# STM32.net
KiCad netlist of a schematic drawn in Altium Designer
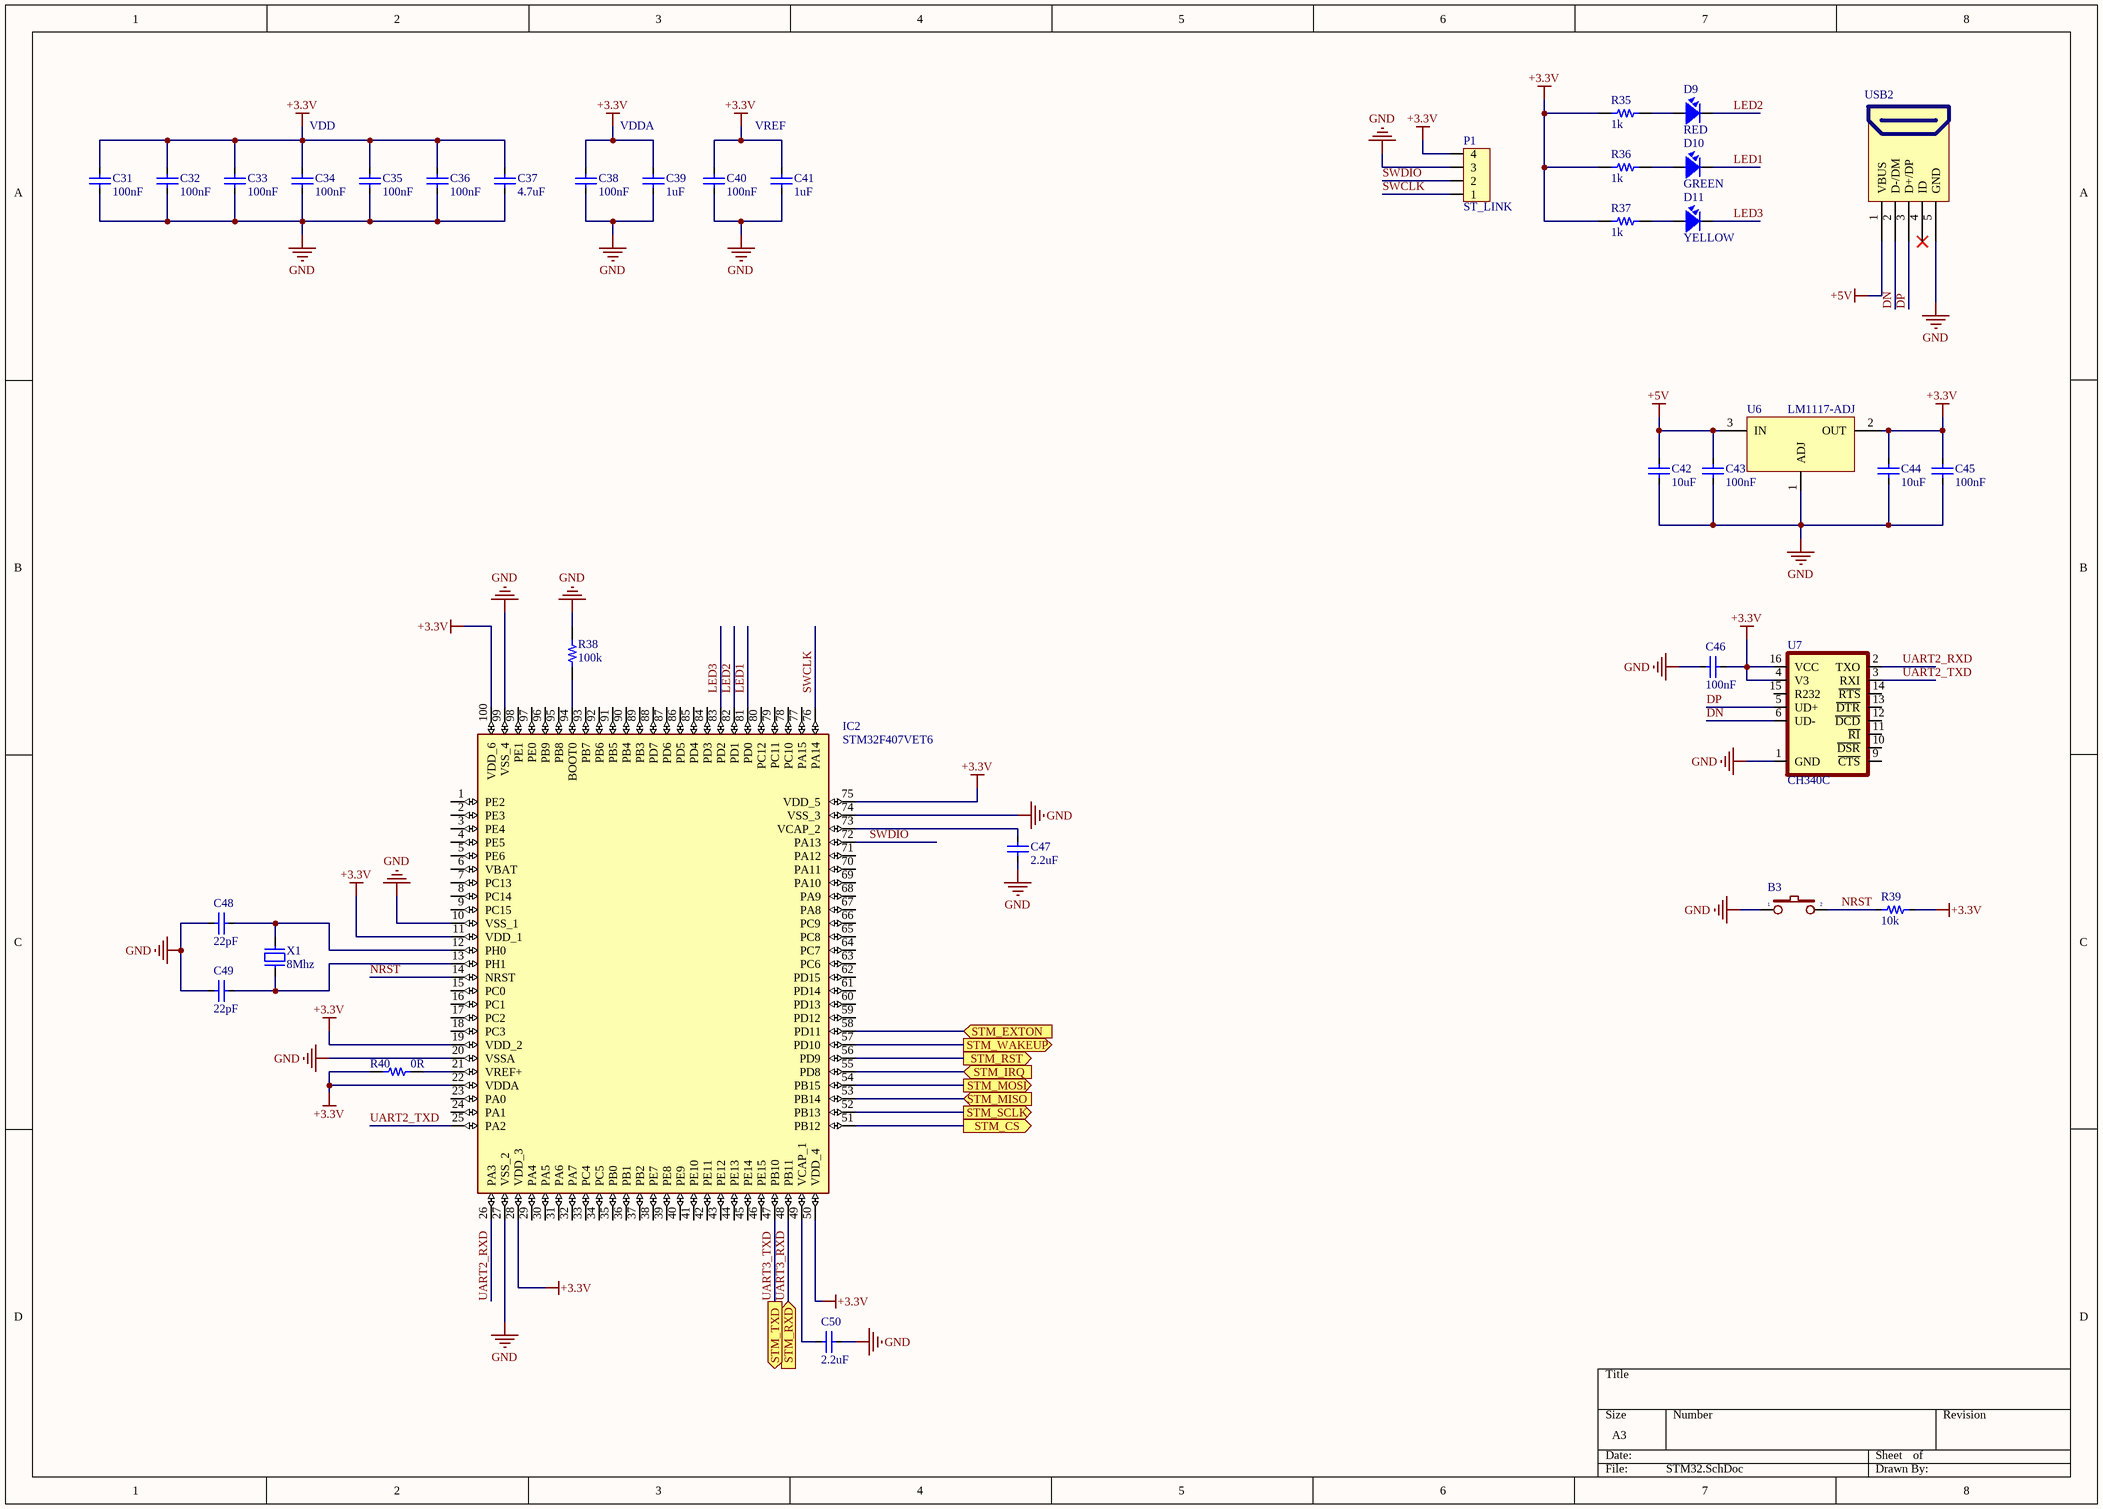
[diagram p0: STM32.SchDoc]

(export (version "E")
  (design (tool "Eeschema 10.0.6"))
  (components
    (comp (ref "B3")
      (value "Button 3x4x2.5")
      (footprint "Button 3x4x2.5")
      (libsource (lib "Dung Library") (part "Button 3x4x2.5"))
    )
    (comp (ref "C31")
      (value "100nF")
      (footprint "CAP_0603")
      (description "Capacitor")
      (fields (field (name "PUBLISHER") "Altium Limited"))
      (libsource (lib "My Library") (part "CapSMD"))
    )
    (comp (ref "C32")
      (value "100nF")
      (footprint "CAP_0603")
      (description "Capacitor")
      (fields (field (name "PUBLISHER") "Altium Limited"))
      (libsource (lib "My Library") (part "CapSMD"))
    )
    (comp (ref "C33")
      (value "100nF")
      (footprint "CAP_0603")
      (description "Capacitor")
      (fields (field (name "PUBLISHER") "Altium Limited"))
      (libsource (lib "My Library") (part "CapSMD"))
    )
    (comp (ref "C34")
      (value "100nF")
      (footprint "CAP_0603")
      (description "Capacitor")
      (fields (field (name "PUBLISHER") "Altium Limited"))
      (libsource (lib "My Library") (part "CapSMD"))
    )
    (comp (ref "C35")
      (value "100nF")
      (footprint "CAP_0603")
      (description "Capacitor")
      (fields (field (name "PUBLISHER") "Altium Limited"))
      (libsource (lib "My Library") (part "CapSMD"))
    )
    (comp (ref "C36")
      (value "100nF")
      (footprint "CAP_0603")
      (description "Capacitor")
      (fields (field (name "PUBLISHER") "Altium Limited"))
      (libsource (lib "My Library") (part "CapSMD"))
    )
    (comp (ref "C37")
      (value "4.7uF")
      (footprint "CAP_0603")
      (description "Capacitor")
      (fields (field (name "PUBLISHER") "Altium Limited"))
      (libsource (lib "My Library") (part "CapSMD"))
    )
    (comp (ref "C38")
      (value "100nF")
      (footprint "CAP_0603")
      (description "Capacitor")
      (fields (field (name "PUBLISHER") "Altium Limited"))
      (libsource (lib "My Library") (part "CapSMD"))
    )
    (comp (ref "C39")
      (value "1uF")
      (footprint "CAP_0603")
      (description "Capacitor")
      (fields (field (name "PUBLISHER") "Altium Limited"))
      (libsource (lib "My Library") (part "CapSMD"))
    )
    (comp (ref "C40")
      (value "100nF")
      (footprint "CAP_0603")
      (description "Capacitor")
      (fields (field (name "PUBLISHER") "Altium Limited"))
      (libsource (lib "My Library") (part "CapSMD"))
    )
    (comp (ref "C41")
      (value "1uF")
      (footprint "CAP_0603")
      (description "Capacitor")
      (fields (field (name "PUBLISHER") "Altium Limited"))
      (libsource (lib "My Library") (part "CapSMD"))
    )
    (comp (ref "C42")
      (value "10uF")
      (footprint "CAP_0603")
      (description "Capacitor")
      (fields (field (name "PUBLISHER") "Altium Limited"))
      (libsource (lib "My Library") (part "CapSMD"))
    )
    (comp (ref "C43")
      (value "100nF")
      (footprint "CAP_0603")
      (description "Capacitor")
      (fields (field (name "PUBLISHER") "Altium Limited"))
      (libsource (lib "My Library") (part "CapSMD"))
    )
    (comp (ref "C44")
      (value "10uF")
      (footprint "CAP_0603")
      (description "Capacitor")
      (fields (field (name "PUBLISHER") "Altium Limited"))
      (libsource (lib "My Library") (part "CapSMD"))
    )
    (comp (ref "C45")
      (value "100nF")
      (footprint "CAP_0603")
      (description "Capacitor")
      (fields (field (name "PUBLISHER") "Altium Limited"))
      (libsource (lib "My Library") (part "CapSMD"))
    )
    (comp (ref "C46")
      (value "100nF")
      (footprint "CAP_0603")
      (description "Capacitor")
      (fields (field (name "PUBLISHER") "Altium Limited"))
      (libsource (lib "My Library") (part "CapSMD"))
    )
    (comp (ref "C47")
      (value "2.2uF")
      (footprint "CAP_0603")
      (description "Capacitor")
      (fields (field (name "PUBLISHER") "Altium Limited"))
      (libsource (lib "My Library") (part "CapSMD"))
    )
    (comp (ref "C48")
      (value "22pF")
      (footprint "CAP_0603")
      (description "Capacitor")
      (fields (field (name "PUBLISHER") "Altium Limited"))
      (libsource (lib "My Library") (part "CapSMD"))
    )
    (comp (ref "C49")
      (value "22pF")
      (footprint "CAP_0603")
      (description "Capacitor")
      (fields (field (name "PUBLISHER") "Altium Limited"))
      (libsource (lib "My Library") (part "CapSMD"))
    )
    (comp (ref "C50")
      (value "2.2uF")
      (footprint "CAP_0603")
      (description "Capacitor")
      (fields (field (name "PUBLISHER") "Altium Limited"))
      (libsource (lib "My Library") (part "CapSMD"))
    )
    (comp (ref "D9")
      (value "RED")
      (footprint "LED-0603-Red")
      (description "LED Single colour Green and Red")
      (libsource (lib "My Library") (part "LED"))
    )
    (comp (ref "D10")
      (value "GREEN")
      (footprint "LED-0603-Green")
      (description "LED Single colour Green and Red")
      (libsource (lib "My Library") (part "LED"))
    )
    (comp (ref "D11")
      (value "YELLOW")
      (footprint "LED-0603-Red")
      (description "LED Single colour Green and Red")
      (libsource (lib "My Library") (part "LED"))
    )
    (comp (ref "IC2")
      (value "STM32F407VET6")
      (footprint "STM32F407VET6")
      (libsource (lib "Dung Library") (part "STM32F407VET6"))
    )
    (comp (ref "P1")
      (value "ST_LINK")
      (footprint "HEADER4P-1.25")
      (description "Header IDC, 4 x 1 Pin Vertical 2.54mm Pitch (Non-Boxed, Male)")
      (fields
        (field (name "MANUFACTURER") "Würth Elektronik eiSos GmbH")
        (field (name "PARTNO") "613002143121")
        (field (name "CREATED BY") "Karrer Zheng")
      )
      (libsource (lib "My Library") (part "Header4"))
    )
    (comp (ref "R35")
      (value "1k")
      (footprint "RES-SMD-0603")
      (description "Resistor")
      (fields
        (field (name "MANUFACTURER") "Generic Components")
        (field (name "PUBLISHER") "Altium Hobart Technology Centre")
      )
      (libsource (lib "") (part "Resistor - SMD_1"))
    )
    (comp (ref "R36")
      (value "1k")
      (footprint "RES-SMD-0603")
      (description "Resistor")
      (fields
        (field (name "MANUFACTURER") "Generic Components")
        (field (name "PUBLISHER") "Altium Hobart Technology Centre")
      )
      (libsource (lib "") (part "Resistor - SMD_1"))
    )
    (comp (ref "R37")
      (value "1k")
      (footprint "RES-SMD-0603")
      (description "Resistor")
      (fields
        (field (name "MANUFACTURER") "Generic Components")
        (field (name "PUBLISHER") "Altium Hobart Technology Centre")
      )
      (libsource (lib "") (part "Resistor - SMD_1"))
    )
    (comp (ref "R38")
      (value "100k")
      (footprint "RES-SMD-0603")
      (description "Resistor")
      (fields
        (field (name "MANUFACTURER") "Generic Components")
        (field (name "PUBLISHER") "Altium Hobart Technology Centre")
      )
      (libsource (lib "") (part "Resistor - SMD_1"))
    )
    (comp (ref "R39")
      (value "10k")
      (footprint "RES-SMD-0603")
      (description "Resistor")
      (fields
        (field (name "MANUFACTURER") "Generic Components")
        (field (name "PUBLISHER") "Altium Hobart Technology Centre")
      )
      (libsource (lib "My Library") (part "Resistor - SMD"))
    )
    (comp (ref "R40")
      (value "0R")
      (footprint "RES-SMD-0603")
      (description "Resistor")
      (fields
        (field (name "MANUFACTURER") "Generic Components")
        (field (name "PUBLISHER") "Altium Hobart Technology Centre")
      )
      (libsource (lib "") (part "Resistor - SMD_1"))
    )
    (comp (ref "U6")
      (value "LM1117-ADJ")
      (footprint "LM1117-SOP")
      (description "800mA Low-Dropout Linear Regulator")
      (fields (field (name "CREATOR") "Nguyen Ba Bien"))
      (libsource (lib "My Library") (part "LM1117-ADJ"))
    )
    (comp (ref "U7")
      (value "CH340C")
      (footprint "SO16")
      (description "USB to serial chip CH340")
      (fields (field (name "MF") "WCH"))
      (libsource (lib "My Library") (part "CH340C"))
    )
    (comp (ref "USB2")
      (value "USB Micro 5p DIP")
      (footprint "USB Micro 5p DIP")
      (description "USB Type B")
      (libsource (lib "Altium_Lib_by_KhueNguyenCreator") (part "USB Micro 5p DIP"))
    )
    (comp (ref "X1")
      (value "8Mhz")
      (footprint "XTAL 5032 SMD")
      (description "Crystal For all Crystal 2pin.")
      (libsource (lib "My Library") (part "XT2"))
    )
  )
  (nets
    (net (code "1") (name "+3.3V") (class "Default")
      (node (ref "C31") (pin "2") (pinfunction "2_2") (pintype "passive"))
      (node (ref "C32") (pin "2") (pinfunction "2_2") (pintype "passive"))
      (node (ref "C33") (pin "2") (pinfunction "2_2") (pintype "passive"))
      (node (ref "C34") (pin "2") (pinfunction "2_2") (pintype "passive"))
      (node (ref "C35") (pin "2") (pinfunction "2_2") (pintype "passive"))
      (node (ref "C36") (pin "2") (pinfunction "2_2") (pintype "passive"))
      (node (ref "C37") (pin "2") (pinfunction "2_2") (pintype "passive"))
      (node (ref "C38") (pin "2") (pinfunction "2_2") (pintype "passive"))
      (node (ref "C39") (pin "2") (pinfunction "2_2") (pintype "passive"))
      (node (ref "C40") (pin "2") (pinfunction "2_2") (pintype "passive"))
      (node (ref "C41") (pin "2") (pinfunction "2_2") (pintype "passive"))
      (node (ref "C44") (pin "1") (pinfunction "1_1") (pintype "passive"))
      (node (ref "C45") (pin "1") (pinfunction "1_1") (pintype "passive"))
      (node (ref "C46") (pin "1") (pinfunction "1_1") (pintype "passive"))
      (node (ref "IC2") (pin "100") (pinfunction "VDD_6_100") (pintype "bidirectional"))
      (node (ref "IC2") (pin "11") (pinfunction "VDD_1_11") (pintype "bidirectional"))
      (node (ref "IC2") (pin "19") (pinfunction "VDD_2_19") (pintype "bidirectional"))
      (node (ref "IC2") (pin "22") (pinfunction "VDDA_22") (pintype "bidirectional"))
      (node (ref "IC2") (pin "28") (pinfunction "VDD_3_28") (pintype "bidirectional"))
      (node (ref "IC2") (pin "50") (pinfunction "VDD_4_50") (pintype "bidirectional"))
      (node (ref "IC2") (pin "75") (pinfunction "VDD_5_75") (pintype "bidirectional"))
      (node (ref "P1") (pin "4") (pinfunction "4_4") (pintype "passive"))
      (node (ref "R35") (pin "2") (pinfunction "2_2") (pintype "passive"))
      (node (ref "R36") (pin "2") (pinfunction "2_2") (pintype "passive"))
      (node (ref "R37") (pin "2") (pinfunction "2_2") (pintype "passive"))
      (node (ref "R39") (pin "1") (pinfunction "1_1") (pintype "passive"))
      (node (ref "R40") (pin "2") (pinfunction "2_2") (pintype "passive"))
      (node (ref "U6") (pin "2") (pinfunction "OUT_2") (pintype "passive"))
      (node (ref "U7") (pin "16") (pinfunction "VCC_16") (pintype "bidirectional"))
      (node (ref "U7") (pin "4") (pinfunction "V3_4") (pintype "bidirectional"))
    )
    (net (code "2") (name "+5V") (class "Default")
      (node (ref "C42") (pin "1") (pinfunction "1_1") (pintype "passive"))
      (node (ref "C43") (pin "1") (pinfunction "1_1") (pintype "passive"))
      (node (ref "U6") (pin "3") (pinfunction "IN_3") (pintype "passive"))
      (node (ref "USB2") (pin "1") (pinfunction "VBUS_1") (pintype "passive"))
    )
    (net (code "3") (name "/DN") (class "Default")
      (node (ref "U7") (pin "6") (pinfunction "UD-_6") (pintype "bidirectional"))
      (node (ref "USB2") (pin "2") (pinfunction "D-/DM_2") (pintype "passive"))
    )
    (net (code "4") (name "/DP") (class "Default")
      (node (ref "U7") (pin "5") (pinfunction "UD+_5") (pintype "bidirectional"))
      (node (ref "USB2") (pin "3") (pinfunction "D+/DP_3") (pintype "passive"))
    )
    (net (code "5") (name "/LED1") (class "Default")
      (node (ref "D10") (pin "2") (pinfunction "2_2") (pintype "passive"))
      (node (ref "IC2") (pin "81") (pinfunction "PD0_81") (pintype "bidirectional"))
    )
    (net (code "6") (name "/LED2") (class "Default")
      (node (ref "D9") (pin "2") (pinfunction "2_2") (pintype "passive"))
      (node (ref "IC2") (pin "82") (pinfunction "PD1_82") (pintype "bidirectional"))
    )
    (net (code "7") (name "/LED3") (class "Default")
      (node (ref "D11") (pin "2") (pinfunction "2_2") (pintype "passive"))
      (node (ref "IC2") (pin "83") (pinfunction "PD2_83") (pintype "bidirectional"))
    )
    (net (code "8") (name "/NRST") (class "Default")
      (node (ref "B3") (pin "2") (pinfunction "2_2") (pintype "passive"))
      (node (ref "IC2") (pin "14") (pinfunction "NRST_14") (pintype "bidirectional"))
      (node (ref "R39") (pin "2") (pinfunction "2_2") (pintype "passive"))
    )
    (net (code "9") (name "/STM_CS") (class "Default")
      (node (ref "IC2") (pin "51") (pinfunction "PB12_51") (pintype "bidirectional"))
    )
    (net (code "10") (name "/STM_EXTON") (class "Default")
      (node (ref "IC2") (pin "58") (pinfunction "PD11_58") (pintype "bidirectional"))
    )
    (net (code "11") (name "/STM_IRQ") (class "Default")
      (node (ref "IC2") (pin "55") (pinfunction "PD8_55") (pintype "bidirectional"))
    )
    (net (code "12") (name "/STM_MISO") (class "Default")
      (node (ref "IC2") (pin "53") (pinfunction "PB14_53") (pintype "bidirectional"))
    )
    (net (code "13") (name "/STM_MOSI") (class "Default")
      (node (ref "IC2") (pin "54") (pinfunction "PB15_54") (pintype "bidirectional"))
    )
    (net (code "14") (name "/STM_RST") (class "Default")
      (node (ref "IC2") (pin "56") (pinfunction "PD9_56") (pintype "bidirectional"))
    )
    (net (code "15") (name "/STM_SCLK") (class "Default")
      (node (ref "IC2") (pin "52") (pinfunction "PB13_52") (pintype "bidirectional"))
    )
    (net (code "16") (name "/STM_WAKEUP") (class "Default")
      (node (ref "IC2") (pin "57") (pinfunction "PD10_57") (pintype "bidirectional"))
    )
    (net (code "17") (name "/SWCLK") (class "Default")
      (node (ref "IC2") (pin "76") (pinfunction "PA14_76") (pintype "bidirectional"))
      (node (ref "P1") (pin "1") (pinfunction "1_1") (pintype "passive"))
    )
    (net (code "18") (name "/SWDIO") (class "Default")
      (node (ref "IC2") (pin "72") (pinfunction "PA13_72") (pintype "bidirectional"))
      (node (ref "P1") (pin "2") (pinfunction "2_2") (pintype "passive"))
    )
    (net (code "19") (name "/UART2_RXD") (class "Default")
      (node (ref "IC2") (pin "26") (pinfunction "PA3_26") (pintype "bidirectional"))
      (node (ref "U7") (pin "2") (pinfunction "TXO_2") (pintype "bidirectional"))
    )
    (net (code "20") (name "/UART2_TXD") (class "Default")
      (node (ref "IC2") (pin "25") (pinfunction "PA2_25") (pintype "bidirectional"))
      (node (ref "U7") (pin "3") (pinfunction "RXI_3") (pintype "bidirectional"))
    )
    (net (code "21") (name "/UART3_RXD") (class "Default")
      (node (ref "IC2") (pin "48") (pinfunction "PB11_48") (pintype "bidirectional"))
    )
    (net (code "22") (name "/UART3_TXD") (class "Default")
      (node (ref "IC2") (pin "47") (pinfunction "PB10_47") (pintype "bidirectional"))
    )
    (net (code "23") (name "GND") (class "Default")
      (node (ref "B3") (pin "1") (pinfunction "1_1") (pintype "passive"))
      (node (ref "C31") (pin "1") (pinfunction "1_1") (pintype "passive"))
      (node (ref "C32") (pin "1") (pinfunction "1_1") (pintype "passive"))
      (node (ref "C33") (pin "1") (pinfunction "1_1") (pintype "passive"))
      (node (ref "C34") (pin "1") (pinfunction "1_1") (pintype "passive"))
      (node (ref "C35") (pin "1") (pinfunction "1_1") (pintype "passive"))
      (node (ref "C36") (pin "1") (pinfunction "1_1") (pintype "passive"))
      (node (ref "C37") (pin "1") (pinfunction "1_1") (pintype "passive"))
      (node (ref "C38") (pin "1") (pinfunction "1_1") (pintype "passive"))
      (node (ref "C39") (pin "1") (pinfunction "1_1") (pintype "passive"))
      (node (ref "C40") (pin "1") (pinfunction "1_1") (pintype "passive"))
      (node (ref "C41") (pin "1") (pinfunction "1_1") (pintype "passive"))
      (node (ref "C42") (pin "2") (pinfunction "2_2") (pintype "passive"))
      (node (ref "C43") (pin "2") (pinfunction "2_2") (pintype "passive"))
      (node (ref "C44") (pin "2") (pinfunction "2_2") (pintype "passive"))
      (node (ref "C45") (pin "2") (pinfunction "2_2") (pintype "passive"))
      (node (ref "C46") (pin "2") (pinfunction "2_2") (pintype "passive"))
      (node (ref "C47") (pin "2") (pinfunction "2_2") (pintype "passive"))
      (node (ref "C48") (pin "1") (pinfunction "1_1") (pintype "passive"))
      (node (ref "C49") (pin "1") (pinfunction "1_1") (pintype "passive"))
      (node (ref "C50") (pin "2") (pinfunction "2_2") (pintype "passive"))
      (node (ref "IC2") (pin "10") (pinfunction "VSS_1_10") (pintype "bidirectional"))
      (node (ref "IC2") (pin "20") (pinfunction "VSSA_20") (pintype "bidirectional"))
      (node (ref "IC2") (pin "27") (pinfunction "VSS_2_27") (pintype "bidirectional"))
      (node (ref "IC2") (pin "74") (pinfunction "VSS_3_74") (pintype "bidirectional"))
      (node (ref "IC2") (pin "99") (pinfunction "VSS_4_99") (pintype "bidirectional"))
      (node (ref "P1") (pin "3") (pinfunction "3_3") (pintype "passive"))
      (node (ref "R38") (pin "1") (pinfunction "1_1") (pintype "passive"))
      (node (ref "U6") (pin "1") (pinfunction "ADJ_1") (pintype "passive"))
      (node (ref "U7") (pin "1") (pinfunction "GND_1") (pintype "bidirectional"))
      (node (ref "USB2") (pin "5") (pinfunction "GND_5") (pintype "passive"))
    )
    (net (code "24") (name "Net-(D9-Pad1)") (class "Default")
      (node (ref "D9") (pin "1") (pinfunction "1_1") (pintype "passive"))
      (node (ref "R35") (pin "1") (pinfunction "1_1") (pintype "passive"))
    )
    (net (code "25") (name "Net-(D10-Pad1)") (class "Default")
      (node (ref "D10") (pin "1") (pinfunction "1_1") (pintype "passive"))
      (node (ref "R36") (pin "1") (pinfunction "1_1") (pintype "passive"))
    )
    (net (code "26") (name "Net-(D11-Pad1)") (class "Default")
      (node (ref "D11") (pin "1") (pinfunction "1_1") (pintype "passive"))
      (node (ref "R37") (pin "1") (pinfunction "1_1") (pintype "passive"))
    )
    (net (code "27") (name "Net-(IC2-BOOT0)") (class "Default")
      (node (ref "IC2") (pin "94") (pinfunction "BOOT0_94") (pintype "bidirectional"))
      (node (ref "R38") (pin "2") (pinfunction "2_2") (pintype "passive"))
    )
    (net (code "28") (name "Net-(IC2-PH0)") (class "Default")
      (node (ref "C48") (pin "2") (pinfunction "2_2") (pintype "passive"))
      (node (ref "IC2") (pin "12") (pinfunction "PH0_12") (pintype "bidirectional"))
      (node (ref "X1") (pin "1") (pinfunction "1_1") (pintype "passive"))
    )
    (net (code "29") (name "Net-(IC2-PH1)") (class "Default")
      (node (ref "C49") (pin "2") (pinfunction "2_2") (pintype "passive"))
      (node (ref "IC2") (pin "13") (pinfunction "PH1_13") (pintype "bidirectional"))
      (node (ref "X1") (pin "2") (pinfunction "2_2") (pintype "passive"))
    )
    (net (code "30") (name "Net-(IC2-VCAP_1)") (class "Default")
      (node (ref "C50") (pin "1") (pinfunction "1_1") (pintype "passive"))
      (node (ref "IC2") (pin "49") (pinfunction "VCAP_1_49") (pintype "bidirectional"))
    )
    (net (code "31") (name "Net-(IC2-VCAP_2)") (class "Default")
      (node (ref "C47") (pin "1") (pinfunction "1_1") (pintype "passive"))
      (node (ref "IC2") (pin "73") (pinfunction "VCAP_2_73") (pintype "bidirectional"))
    )
    (net (code "32") (name "Net-(IC2-VREF+)") (class "Default")
      (node (ref "IC2") (pin "21") (pinfunction "VREF+_21") (pintype "bidirectional"))
      (node (ref "R40") (pin "1") (pinfunction "1_1") (pintype "passive"))
    )
    (net (code "33") (name "unconnected-(IC2-PA0-Pad23)") (class "Default")
      (node (ref "IC2") (pin "23") (pinfunction "PA0_23") (pintype "bidirectional"))
    )
    (net (code "34") (name "unconnected-(IC2-PA1-Pad24)") (class "Default")
      (node (ref "IC2") (pin "24") (pinfunction "PA1_24") (pintype "bidirectional"))
    )
    (net (code "35") (name "unconnected-(IC2-PA4-Pad29)") (class "Default")
      (node (ref "IC2") (pin "29") (pinfunction "PA4_29") (pintype "bidirectional"))
    )
    (net (code "36") (name "unconnected-(IC2-PA5-Pad30)") (class "Default")
      (node (ref "IC2") (pin "30") (pinfunction "PA5_30") (pintype "bidirectional"))
    )
    (net (code "37") (name "unconnected-(IC2-PA6-Pad31)") (class "Default")
      (node (ref "IC2") (pin "31") (pinfunction "PA6_31") (pintype "bidirectional"))
    )
    (net (code "38") (name "unconnected-(IC2-PA7-Pad32)") (class "Default")
      (node (ref "IC2") (pin "32") (pinfunction "PA7_32") (pintype "bidirectional"))
    )
    (net (code "39") (name "unconnected-(IC2-PA8-Pad67)") (class "Default")
      (node (ref "IC2") (pin "67") (pinfunction "PA8_67") (pintype "bidirectional"))
    )
    (net (code "40") (name "unconnected-(IC2-PA9-Pad68)") (class "Default")
      (node (ref "IC2") (pin "68") (pinfunction "PA9_68") (pintype "bidirectional"))
    )
    (net (code "41") (name "unconnected-(IC2-PA10-Pad69)") (class "Default")
      (node (ref "IC2") (pin "69") (pinfunction "PA10_69") (pintype "bidirectional"))
    )
    (net (code "42") (name "unconnected-(IC2-PA11-Pad70)") (class "Default")
      (node (ref "IC2") (pin "70") (pinfunction "PA11_70") (pintype "bidirectional"))
    )
    (net (code "43") (name "unconnected-(IC2-PA12-Pad71)") (class "Default")
      (node (ref "IC2") (pin "71") (pinfunction "PA12_71") (pintype "bidirectional"))
    )
    (net (code "44") (name "unconnected-(IC2-PA15-Pad77)") (class "Default")
      (node (ref "IC2") (pin "77") (pinfunction "PA15_77") (pintype "bidirectional"))
    )
    (net (code "45") (name "unconnected-(IC2-PB0-Pad35)") (class "Default")
      (node (ref "IC2") (pin "35") (pinfunction "PB0_35") (pintype "bidirectional"))
    )
    (net (code "46") (name "unconnected-(IC2-PB1-Pad36)") (class "Default")
      (node (ref "IC2") (pin "36") (pinfunction "PB1_36") (pintype "bidirectional"))
    )
    (net (code "47") (name "unconnected-(IC2-PB2-Pad37)") (class "Default")
      (node (ref "IC2") (pin "37") (pinfunction "PB2_37") (pintype "bidirectional"))
    )
    (net (code "48") (name "unconnected-(IC2-PB3-Pad89)") (class "Default")
      (node (ref "IC2") (pin "89") (pinfunction "PB3_89") (pintype "bidirectional"))
    )
    (net (code "49") (name "unconnected-(IC2-PB4-Pad90)") (class "Default")
      (node (ref "IC2") (pin "90") (pinfunction "PB4_90") (pintype "bidirectional"))
    )
    (net (code "50") (name "unconnected-(IC2-PB5-Pad91)") (class "Default")
      (node (ref "IC2") (pin "91") (pinfunction "PB5_91") (pintype "bidirectional"))
    )
    (net (code "51") (name "unconnected-(IC2-PB6-Pad92)") (class "Default")
      (node (ref "IC2") (pin "92") (pinfunction "PB6_92") (pintype "bidirectional"))
    )
    (net (code "52") (name "unconnected-(IC2-PB7-Pad93)") (class "Default")
      (node (ref "IC2") (pin "93") (pinfunction "PB7_93") (pintype "bidirectional"))
    )
    (net (code "53") (name "unconnected-(IC2-PB8-Pad95)") (class "Default")
      (node (ref "IC2") (pin "95") (pinfunction "PB8_95") (pintype "bidirectional"))
    )
    (net (code "54") (name "unconnected-(IC2-PB9-Pad96)") (class "Default")
      (node (ref "IC2") (pin "96") (pinfunction "PB9_96") (pintype "bidirectional"))
    )
    (net (code "55") (name "unconnected-(IC2-PC0-Pad15)") (class "Default")
      (node (ref "IC2") (pin "15") (pinfunction "PC0_15") (pintype "bidirectional"))
    )
    (net (code "56") (name "unconnected-(IC2-PC1-Pad16)") (class "Default")
      (node (ref "IC2") (pin "16") (pinfunction "PC1_16") (pintype "bidirectional"))
    )
    (net (code "57") (name "unconnected-(IC2-PC2-Pad17)") (class "Default")
      (node (ref "IC2") (pin "17") (pinfunction "PC2_17") (pintype "bidirectional"))
    )
    (net (code "58") (name "unconnected-(IC2-PC3-Pad18)") (class "Default")
      (node (ref "IC2") (pin "18") (pinfunction "PC3_18") (pintype "bidirectional"))
    )
    (net (code "59") (name "unconnected-(IC2-PC4-Pad33)") (class "Default")
      (node (ref "IC2") (pin "33") (pinfunction "PC4_33") (pintype "bidirectional"))
    )
    (net (code "60") (name "unconnected-(IC2-PC5-Pad34)") (class "Default")
      (node (ref "IC2") (pin "34") (pinfunction "PC5_34") (pintype "bidirectional"))
    )
    (net (code "61") (name "unconnected-(IC2-PC6-Pad63)") (class "Default")
      (node (ref "IC2") (pin "63") (pinfunction "PC6_63") (pintype "bidirectional"))
    )
    (net (code "62") (name "unconnected-(IC2-PC7-Pad64)") (class "Default")
      (node (ref "IC2") (pin "64") (pinfunction "PC7_64") (pintype "bidirectional"))
    )
    (net (code "63") (name "unconnected-(IC2-PC8-Pad65)") (class "Default")
      (node (ref "IC2") (pin "65") (pinfunction "PC8_65") (pintype "bidirectional"))
    )
    (net (code "64") (name "unconnected-(IC2-PC9-Pad66)") (class "Default")
      (node (ref "IC2") (pin "66") (pinfunction "PC9_66") (pintype "bidirectional"))
    )
    (net (code "65") (name "unconnected-(IC2-PC10-Pad78)") (class "Default")
      (node (ref "IC2") (pin "78") (pinfunction "PC10_78") (pintype "bidirectional"))
    )
    (net (code "66") (name "unconnected-(IC2-PC11-Pad79)") (class "Default")
      (node (ref "IC2") (pin "79") (pinfunction "PC11_79") (pintype "bidirectional"))
    )
    (net (code "67") (name "unconnected-(IC2-PC12-Pad80)") (class "Default")
      (node (ref "IC2") (pin "80") (pinfunction "PC12_80") (pintype "bidirectional"))
    )
    (net (code "68") (name "unconnected-(IC2-PC13-Pad7)") (class "Default")
      (node (ref "IC2") (pin "7") (pinfunction "PC13_7") (pintype "bidirectional"))
    )
    (net (code "69") (name "unconnected-(IC2-PC14-Pad8)") (class "Default")
      (node (ref "IC2") (pin "8") (pinfunction "PC14_8") (pintype "bidirectional"))
    )
    (net (code "70") (name "unconnected-(IC2-PC15-Pad9)") (class "Default")
      (node (ref "IC2") (pin "9") (pinfunction "PC15_9") (pintype "bidirectional"))
    )
    (net (code "71") (name "unconnected-(IC2-PD3-Pad84)") (class "Default")
      (node (ref "IC2") (pin "84") (pinfunction "PD3_84") (pintype "bidirectional"))
    )
    (net (code "72") (name "unconnected-(IC2-PD4-Pad85)") (class "Default")
      (node (ref "IC2") (pin "85") (pinfunction "PD4_85") (pintype "bidirectional"))
    )
    (net (code "73") (name "unconnected-(IC2-PD5-Pad86)") (class "Default")
      (node (ref "IC2") (pin "86") (pinfunction "PD5_86") (pintype "bidirectional"))
    )
    (net (code "74") (name "unconnected-(IC2-PD6-Pad87)") (class "Default")
      (node (ref "IC2") (pin "87") (pinfunction "PD6_87") (pintype "bidirectional"))
    )
    (net (code "75") (name "unconnected-(IC2-PD7-Pad88)") (class "Default")
      (node (ref "IC2") (pin "88") (pinfunction "PD7_88") (pintype "bidirectional"))
    )
    (net (code "76") (name "unconnected-(IC2-PD12-Pad59)") (class "Default")
      (node (ref "IC2") (pin "59") (pinfunction "PD12_59") (pintype "bidirectional"))
    )
    (net (code "77") (name "unconnected-(IC2-PD13-Pad60)") (class "Default")
      (node (ref "IC2") (pin "60") (pinfunction "PD13_60") (pintype "bidirectional"))
    )
    (net (code "78") (name "unconnected-(IC2-PD14-Pad61)") (class "Default")
      (node (ref "IC2") (pin "61") (pinfunction "PD14_61") (pintype "bidirectional"))
    )
    (net (code "79") (name "unconnected-(IC2-PD15-Pad62)") (class "Default")
      (node (ref "IC2") (pin "62") (pinfunction "PD15_62") (pintype "bidirectional"))
    )
    (net (code "80") (name "unconnected-(IC2-PE0-Pad97)") (class "Default")
      (node (ref "IC2") (pin "97") (pinfunction "PE0_97") (pintype "bidirectional"))
    )
    (net (code "81") (name "unconnected-(IC2-PE1-Pad98)") (class "Default")
      (node (ref "IC2") (pin "98") (pinfunction "PE1_98") (pintype "bidirectional"))
    )
    (net (code "82") (name "unconnected-(IC2-PE2-Pad1)") (class "Default")
      (node (ref "IC2") (pin "1") (pinfunction "PE2_1") (pintype "bidirectional"))
    )
    (net (code "83") (name "unconnected-(IC2-PE3-Pad2)") (class "Default")
      (node (ref "IC2") (pin "2") (pinfunction "PE3_2") (pintype "bidirectional"))
    )
    (net (code "84") (name "unconnected-(IC2-PE4-Pad3)") (class "Default")
      (node (ref "IC2") (pin "3") (pinfunction "PE4_3") (pintype "bidirectional"))
    )
    (net (code "85") (name "unconnected-(IC2-PE5-Pad4)") (class "Default")
      (node (ref "IC2") (pin "4") (pinfunction "PE5_4") (pintype "bidirectional"))
    )
    (net (code "86") (name "unconnected-(IC2-PE6-Pad5)") (class "Default")
      (node (ref "IC2") (pin "5") (pinfunction "PE6_5") (pintype "bidirectional"))
    )
    (net (code "87") (name "unconnected-(IC2-PE7-Pad38)") (class "Default")
      (node (ref "IC2") (pin "38") (pinfunction "PE7_38") (pintype "bidirectional"))
    )
    (net (code "88") (name "unconnected-(IC2-PE8-Pad39)") (class "Default")
      (node (ref "IC2") (pin "39") (pinfunction "PE8_39") (pintype "bidirectional"))
    )
    (net (code "89") (name "unconnected-(IC2-PE9-Pad40)") (class "Default")
      (node (ref "IC2") (pin "40") (pinfunction "PE9_40") (pintype "bidirectional"))
    )
    (net (code "90") (name "unconnected-(IC2-PE10-Pad41)") (class "Default")
      (node (ref "IC2") (pin "41") (pinfunction "PE10_41") (pintype "bidirectional"))
    )
    (net (code "91") (name "unconnected-(IC2-PE11-Pad42)") (class "Default")
      (node (ref "IC2") (pin "42") (pinfunction "PE11_42") (pintype "bidirectional"))
    )
    (net (code "92") (name "unconnected-(IC2-PE12-Pad43)") (class "Default")
      (node (ref "IC2") (pin "43") (pinfunction "PE12_43") (pintype "bidirectional"))
    )
    (net (code "93") (name "unconnected-(IC2-PE13-Pad44)") (class "Default")
      (node (ref "IC2") (pin "44") (pinfunction "PE13_44") (pintype "bidirectional"))
    )
    (net (code "94") (name "unconnected-(IC2-PE14-Pad45)") (class "Default")
      (node (ref "IC2") (pin "45") (pinfunction "PE14_45") (pintype "bidirectional"))
    )
    (net (code "95") (name "unconnected-(IC2-PE15-Pad46)") (class "Default")
      (node (ref "IC2") (pin "46") (pinfunction "PE15_46") (pintype "bidirectional"))
    )
    (net (code "96") (name "unconnected-(IC2-VBAT-Pad6)") (class "Default")
      (node (ref "IC2") (pin "6") (pinfunction "VBAT_6") (pintype "bidirectional"))
    )
    (net (code "97") (name "unconnected-(U7-R232-Pad15)") (class "Default")
      (node (ref "U7") (pin "15") (pinfunction "R232_15") (pintype "bidirectional"))
    )
    (net (code "98") (name "unconnected-(U7-~{CTS}-Pad9)") (class "Default")
      (node (ref "U7") (pin "9") (pinfunction "~{CTS}_9") (pintype "bidirectional"))
    )
    (net (code "99") (name "unconnected-(U7-~{DCD}-Pad12)") (class "Default")
      (node (ref "U7") (pin "12") (pinfunction "~{DCD}_12") (pintype "bidirectional"))
    )
    (net (code "100") (name "unconnected-(U7-~{DSR}-Pad10)") (class "Default")
      (node (ref "U7") (pin "10") (pinfunction "~{DSR}_10") (pintype "bidirectional"))
    )
    (net (code "101") (name "unconnected-(U7-~{DTR}-Pad13)") (class "Default")
      (node (ref "U7") (pin "13") (pinfunction "~{DTR}_13") (pintype "bidirectional"))
    )
    (net (code "102") (name "unconnected-(U7-~{RI}-Pad11)") (class "Default")
      (node (ref "U7") (pin "11") (pinfunction "~{RI}_11") (pintype "bidirectional"))
    )
    (net (code "103") (name "unconnected-(U7-~{RTS}-Pad14)") (class "Default")
      (node (ref "U7") (pin "14") (pinfunction "~{RTS}_14") (pintype "bidirectional"))
    )
    (net (code "104") (name "unconnected-(USB2-ID-Pad4)") (class "Default")
      (node (ref "USB2") (pin "4") (pinfunction "ID_4") (pintype "passive+no_connect"))
    )
  )
)
